# BT840F_Schematic.net
KiCad netlist of a schematic drawn in EAGLE
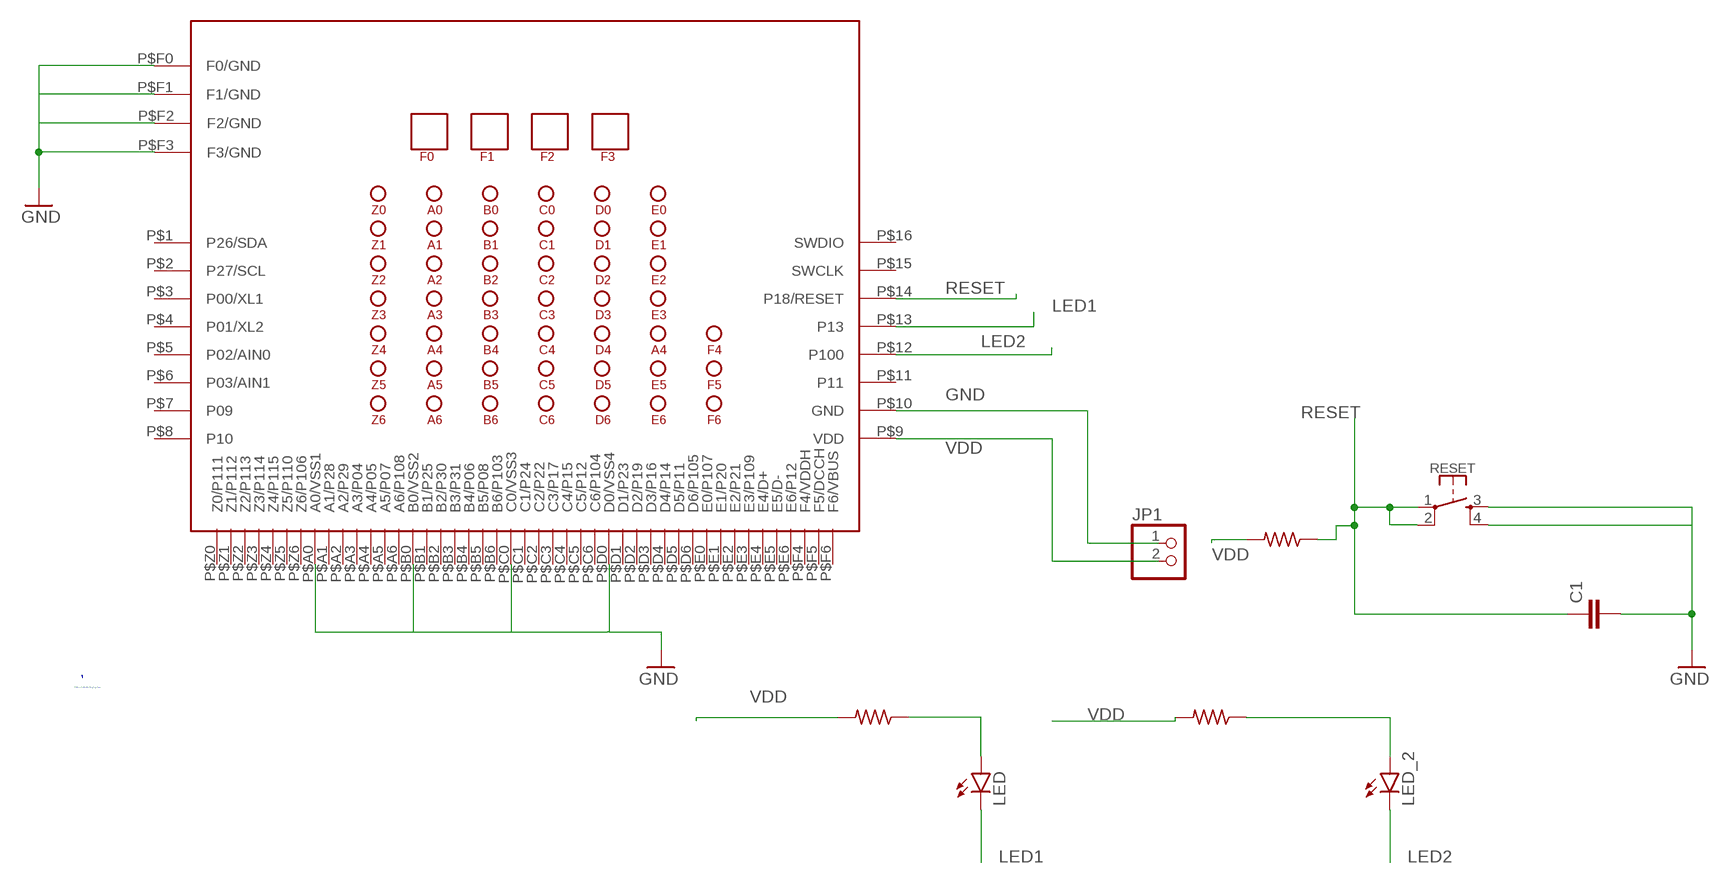
[diagram p0: schematic, sheet 1]

(export (version "E")
  (design (tool "Eeschema 10.0.6"))
  (components
    (comp (ref "C1")
      (value "C-EUC0805")
      (footprint "eagle-import:C0805")
      (libsource (lib "eagle-import") (part "C-EUC0805"))
    )
    (comp (ref "JP1")
      (value "PINHD-1X2")
      (footprint "eagle-import:1X02")
      (libsource (lib "eagle-import") (part "PINHD-1X2"))
    )
    (comp (ref "LED")
      (value "LEDCHIP-LED0805")
      (footprint "eagle-import:CHIP-LED0805")
      (libsource (lib "eagle-import") (part "LEDCHIP-LED0805"))
    )
    (comp (ref "LED_2")
      (value "LEDCHIP-LED0805")
      (footprint "eagle-import:CHIP-LED0805")
      (libsource (lib "eagle-import") (part "LEDCHIP-LED0805"))
    )
    (comp (ref "RESET")
      (value "MOMENTARY-SWITCH-SPST-2-SMD-4.6X2.8MM")
      (footprint "eagle-import:TACTILE_SWITCH_SMD_4.6X2.8MM")
      (libsource (lib "eagle-import") (part "MOMENTARY-SWITCH-SPST-2-SMD-4.6X2.8MM"))
    )
    (comp (ref "R_LED1")
      (value "4.7k")
      (footprint "eagle-import:R0805")
      (libsource (lib "eagle-import") (part "R-US_R0805"))
    )
    (comp (ref "R_LED2")
      (value "4.7k")
      (footprint "eagle-import:R0805")
      (libsource (lib "eagle-import") (part "R-US_R0805"))
    )
    (comp (ref "R_RESET")
      (value "4.7k")
      (footprint "eagle-import:R0805")
      (libsource (lib "eagle-import") (part "R-US_R0805"))
    )
    (comp (ref "U1")
      (value "BT840")
      (footprint "eagle-import:BT840")
      (libsource (lib "eagle-import") (part "BT840"))
    )
  )
  (nets
    (net (code "1") (name "/LED1") (class "Default")
      (node (ref "LED") (pin "C") (pinfunction "C_C") (pintype "passive"))
      (node (ref "U1") (pin "P$13") (pinfunction "P13_P$13") (pintype "bidirectional"))
    )
    (net (code "2") (name "/LED2") (class "Default")
      (node (ref "LED_2") (pin "C") (pinfunction "C_C") (pintype "passive"))
      (node (ref "U1") (pin "P$12") (pinfunction "P100_P$12") (pintype "bidirectional"))
    )
    (net (code "3") (name "/RESET") (class "Default")
      (node (ref "C1") (pin "1") (pinfunction "1_1") (pintype "passive"))
      (node (ref "RESET") (pin "1") (pinfunction "1_1") (pintype "passive"))
      (node (ref "RESET") (pin "2") (pinfunction "2_2") (pintype "passive"))
      (node (ref "R_RESET") (pin "1") (pinfunction "1_1") (pintype "passive"))
      (node (ref "U1") (pin "P$14") (pinfunction "P18/RESET_P$14") (pintype "bidirectional"))
    )
    (net (code "4") (name "/VDD") (class "Default")
      (node (ref "JP1") (pin "2") (pinfunction "2_2") (pintype "passive"))
      (node (ref "R_LED1") (pin "2") (pinfunction "2_2") (pintype "passive"))
      (node (ref "R_LED2") (pin "2") (pinfunction "2_2") (pintype "passive"))
      (node (ref "R_RESET") (pin "2") (pinfunction "2_2") (pintype "passive"))
      (node (ref "U1") (pin "P$9") (pinfunction "VDD_P$9") (pintype "bidirectional"))
    )
    (net (code "5") (name "GND") (class "Default")
      (node (ref "C1") (pin "2") (pinfunction "2_2") (pintype "passive"))
      (node (ref "JP1") (pin "1") (pinfunction "1_1") (pintype "passive"))
      (node (ref "RESET") (pin "3") (pinfunction "3_3") (pintype "passive"))
      (node (ref "RESET") (pin "4") (pinfunction "4_4") (pintype "passive"))
      (node (ref "U1") (pin "P$10") (pinfunction "GND_P$10") (pintype "bidirectional"))
      (node (ref "U1") (pin "P$A0") (pinfunction "A0/VSS1_P$A0") (pintype "bidirectional"))
      (node (ref "U1") (pin "P$B0") (pinfunction "B0/VSS2_P$B0") (pintype "bidirectional"))
      (node (ref "U1") (pin "P$C0") (pinfunction "C0/VSS3_P$C0") (pintype "bidirectional"))
      (node (ref "U1") (pin "P$D0") (pinfunction "D0/VSS4_P$D0") (pintype "bidirectional"))
      (node (ref "U1") (pin "P$F0") (pinfunction "F0/GND_P$F0") (pintype "bidirectional"))
      (node (ref "U1") (pin "P$F1") (pinfunction "F1/GND_P$F1") (pintype "bidirectional"))
      (node (ref "U1") (pin "P$F2") (pinfunction "F2/GND_P$F2") (pintype "bidirectional"))
      (node (ref "U1") (pin "P$F3") (pinfunction "F3/GND_P$F3") (pintype "bidirectional"))
    )
    (net (code "6") (name "Net-(LED-PadA)") (class "Default")
      (node (ref "LED") (pin "A") (pinfunction "A_A") (pintype "passive"))
      (node (ref "R_LED1") (pin "1") (pinfunction "1_1") (pintype "passive"))
    )
    (net (code "7") (name "Net-(LED_2-PadA)") (class "Default")
      (node (ref "LED_2") (pin "A") (pinfunction "A_A") (pintype "passive"))
      (node (ref "R_LED2") (pin "1") (pinfunction "1_1") (pintype "passive"))
    )
    (net (code "8") (name "unconnected-(U1-A1{slash}P28-PadP$A1)") (class "Default")
      (node (ref "U1") (pin "P$A1") (pinfunction "A1/P28_P$A1") (pintype "bidirectional"))
    )
    (net (code "9") (name "unconnected-(U1-A2{slash}P29-PadP$A2)") (class "Default")
      (node (ref "U1") (pin "P$A2") (pinfunction "A2/P29_P$A2") (pintype "bidirectional"))
    )
    (net (code "10") (name "unconnected-(U1-A3{slash}P04-PadP$A3)") (class "Default")
      (node (ref "U1") (pin "P$A3") (pinfunction "A3/P04_P$A3") (pintype "bidirectional"))
    )
    (net (code "11") (name "unconnected-(U1-A4{slash}P05-PadP$A4)") (class "Default")
      (node (ref "U1") (pin "P$A4") (pinfunction "A4/P05_P$A4") (pintype "bidirectional"))
    )
    (net (code "12") (name "unconnected-(U1-A5{slash}P07-PadP$A5)") (class "Default")
      (node (ref "U1") (pin "P$A5") (pinfunction "A5/P07_P$A5") (pintype "bidirectional"))
    )
    (net (code "13") (name "unconnected-(U1-A6{slash}P108-PadP$A6)") (class "Default")
      (node (ref "U1") (pin "P$A6") (pinfunction "A6/P108_P$A6") (pintype "bidirectional"))
    )
    (net (code "14") (name "unconnected-(U1-B1{slash}P25-PadP$B1)") (class "Default")
      (node (ref "U1") (pin "P$B1") (pinfunction "B1/P25_P$B1") (pintype "bidirectional"))
    )
    (net (code "15") (name "unconnected-(U1-B2{slash}P30-PadP$B2)") (class "Default")
      (node (ref "U1") (pin "P$B2") (pinfunction "B2/P30_P$B2") (pintype "bidirectional"))
    )
    (net (code "16") (name "unconnected-(U1-B3{slash}P31-PadP$B3)") (class "Default")
      (node (ref "U1") (pin "P$B3") (pinfunction "B3/P31_P$B3") (pintype "bidirectional"))
    )
    (net (code "17") (name "unconnected-(U1-B4{slash}P06-PadP$B4)") (class "Default")
      (node (ref "U1") (pin "P$B4") (pinfunction "B4/P06_P$B4") (pintype "bidirectional"))
    )
    (net (code "18") (name "unconnected-(U1-B5{slash}P08-PadP$B5)") (class "Default")
      (node (ref "U1") (pin "P$B5") (pinfunction "B5/P08_P$B5") (pintype "bidirectional"))
    )
    (net (code "19") (name "unconnected-(U1-B6{slash}P103-PadP$B6)") (class "Default")
      (node (ref "U1") (pin "P$B6") (pinfunction "B6/P103_P$B6") (pintype "bidirectional"))
    )
    (net (code "20") (name "unconnected-(U1-C1{slash}P24-PadP$C1)") (class "Default")
      (node (ref "U1") (pin "P$C1") (pinfunction "C1/P24_P$C1") (pintype "bidirectional"))
    )
    (net (code "21") (name "unconnected-(U1-C2{slash}P22-PadP$C2)") (class "Default")
      (node (ref "U1") (pin "P$C2") (pinfunction "C2/P22_P$C2") (pintype "bidirectional"))
    )
    (net (code "22") (name "unconnected-(U1-C3{slash}P17-PadP$C3)") (class "Default")
      (node (ref "U1") (pin "P$C3") (pinfunction "C3/P17_P$C3") (pintype "bidirectional"))
    )
    (net (code "23") (name "unconnected-(U1-C4{slash}P15-PadP$C4)") (class "Default")
      (node (ref "U1") (pin "P$C4") (pinfunction "C4/P15_P$C4") (pintype "bidirectional"))
    )
    (net (code "24") (name "unconnected-(U1-C5{slash}P12-PadP$C5)") (class "Default")
      (node (ref "U1") (pin "P$C5") (pinfunction "C5/P12_P$C5") (pintype "bidirectional"))
    )
    (net (code "25") (name "unconnected-(U1-C6{slash}P104-PadP$C6)") (class "Default")
      (node (ref "U1") (pin "P$C6") (pinfunction "C6/P104_P$C6") (pintype "bidirectional"))
    )
    (net (code "26") (name "unconnected-(U1-D1{slash}P23-PadP$D1)") (class "Default")
      (node (ref "U1") (pin "P$D1") (pinfunction "D1/P23_P$D1") (pintype "bidirectional"))
    )
    (net (code "27") (name "unconnected-(U1-D2{slash}P19-PadP$D2)") (class "Default")
      (node (ref "U1") (pin "P$D2") (pinfunction "D2/P19_P$D2") (pintype "bidirectional"))
    )
    (net (code "28") (name "unconnected-(U1-D3{slash}P16-PadP$D3)") (class "Default")
      (node (ref "U1") (pin "P$D3") (pinfunction "D3/P16_P$D3") (pintype "bidirectional"))
    )
    (net (code "29") (name "unconnected-(U1-D4{slash}P14-PadP$D4)") (class "Default")
      (node (ref "U1") (pin "P$D4") (pinfunction "D4/P14_P$D4") (pintype "bidirectional"))
    )
    (net (code "30") (name "unconnected-(U1-D5{slash}P11-PadP$D5)") (class "Default")
      (node (ref "U1") (pin "P$D5") (pinfunction "D5/P11_P$D5") (pintype "bidirectional"))
    )
    (net (code "31") (name "unconnected-(U1-D6{slash}P105-PadP$D6)") (class "Default")
      (node (ref "U1") (pin "P$D6") (pinfunction "D6/P105_P$D6") (pintype "bidirectional"))
    )
    (net (code "32") (name "unconnected-(U1-E0{slash}P107-PadP$E0)") (class "Default")
      (node (ref "U1") (pin "P$E0") (pinfunction "E0/P107_P$E0") (pintype "bidirectional"))
    )
    (net (code "33") (name "unconnected-(U1-E1{slash}P20-PadP$E1)") (class "Default")
      (node (ref "U1") (pin "P$E1") (pinfunction "E1/P20_P$E1") (pintype "bidirectional"))
    )
    (net (code "34") (name "unconnected-(U1-E2{slash}P21-PadP$E2)") (class "Default")
      (node (ref "U1") (pin "P$E2") (pinfunction "E2/P21_P$E2") (pintype "bidirectional"))
    )
    (net (code "35") (name "unconnected-(U1-E3{slash}P109-PadP$E3)") (class "Default")
      (node (ref "U1") (pin "P$E3") (pinfunction "E3/P109_P$E3") (pintype "bidirectional"))
    )
    (net (code "36") (name "unconnected-(U1-E4{slash}D+-PadP$E4)") (class "Default")
      (node (ref "U1") (pin "P$E4") (pinfunction "E4/D+_P$E4") (pintype "bidirectional"))
    )
    (net (code "37") (name "unconnected-(U1-E5{slash}D--PadP$E5)") (class "Default")
      (node (ref "U1") (pin "P$E5") (pinfunction "E5/D-_P$E5") (pintype "bidirectional"))
    )
    (net (code "38") (name "unconnected-(U1-E6{slash}P12-PadP$E6)") (class "Default")
      (node (ref "U1") (pin "P$E6") (pinfunction "E6/P12_P$E6") (pintype "bidirectional"))
    )
    (net (code "39") (name "unconnected-(U1-F4{slash}VDDH-PadP$F4)") (class "Default")
      (node (ref "U1") (pin "P$F4") (pinfunction "F4/VDDH_P$F4") (pintype "bidirectional"))
    )
    (net (code "40") (name "unconnected-(U1-F5{slash}DCCH-PadP$F5)") (class "Default")
      (node (ref "U1") (pin "P$F5") (pinfunction "F5/DCCH_P$F5") (pintype "bidirectional"))
    )
    (net (code "41") (name "unconnected-(U1-F6{slash}VBUS-PadP$F6)") (class "Default")
      (node (ref "U1") (pin "P$F6") (pinfunction "F6/VBUS_P$F6") (pintype "bidirectional"))
    )
    (net (code "42") (name "unconnected-(U1-P00{slash}XL1-PadP$3)") (class "Default")
      (node (ref "U1") (pin "P$3") (pinfunction "P00/XL1_P$3") (pintype "bidirectional"))
    )
    (net (code "43") (name "unconnected-(U1-P01{slash}XL2-PadP$4)") (class "Default")
      (node (ref "U1") (pin "P$4") (pinfunction "P01/XL2_P$4") (pintype "bidirectional"))
    )
    (net (code "44") (name "unconnected-(U1-P02{slash}AIN0-PadP$5)") (class "Default")
      (node (ref "U1") (pin "P$5") (pinfunction "P02/AIN0_P$5") (pintype "bidirectional"))
    )
    (net (code "45") (name "unconnected-(U1-P03{slash}AIN1-PadP$6)") (class "Default")
      (node (ref "U1") (pin "P$6") (pinfunction "P03/AIN1_P$6") (pintype "bidirectional"))
    )
    (net (code "46") (name "unconnected-(U1-P09-PadP$7)") (class "Default")
      (node (ref "U1") (pin "P$7") (pinfunction "P09_P$7") (pintype "bidirectional"))
    )
    (net (code "47") (name "unconnected-(U1-P10-PadP$8)") (class "Default")
      (node (ref "U1") (pin "P$8") (pinfunction "P10_P$8") (pintype "bidirectional"))
    )
    (net (code "48") (name "unconnected-(U1-P11-PadP$11)") (class "Default")
      (node (ref "U1") (pin "P$11") (pinfunction "P11_P$11") (pintype "bidirectional"))
    )
    (net (code "49") (name "unconnected-(U1-P26{slash}SDA-PadP$1)") (class "Default")
      (node (ref "U1") (pin "P$1") (pinfunction "P26/SDA_P$1") (pintype "bidirectional"))
    )
    (net (code "50") (name "unconnected-(U1-P27{slash}SCL-PadP$2)") (class "Default")
      (node (ref "U1") (pin "P$2") (pinfunction "P27/SCL_P$2") (pintype "bidirectional"))
    )
    (net (code "51") (name "unconnected-(U1-SWCLK-PadP$15)") (class "Default")
      (node (ref "U1") (pin "P$15") (pinfunction "SWCLK_P$15") (pintype "bidirectional"))
    )
    (net (code "52") (name "unconnected-(U1-SWDIO-PadP$16)") (class "Default")
      (node (ref "U1") (pin "P$16") (pinfunction "SWDIO_P$16") (pintype "bidirectional"))
    )
    (net (code "53") (name "unconnected-(U1-Z0{slash}P111-PadP$Z0)") (class "Default")
      (node (ref "U1") (pin "P$Z0") (pinfunction "Z0/P111_P$Z0") (pintype "bidirectional"))
    )
    (net (code "54") (name "unconnected-(U1-Z1{slash}P112-PadP$Z1)") (class "Default")
      (node (ref "U1") (pin "P$Z1") (pinfunction "Z1/P112_P$Z1") (pintype "bidirectional"))
    )
    (net (code "55") (name "unconnected-(U1-Z2{slash}P113-PadP$Z2)") (class "Default")
      (node (ref "U1") (pin "P$Z2") (pinfunction "Z2/P113_P$Z2") (pintype "bidirectional"))
    )
    (net (code "56") (name "unconnected-(U1-Z3{slash}P114-PadP$Z3)") (class "Default")
      (node (ref "U1") (pin "P$Z3") (pinfunction "Z3/P114_P$Z3") (pintype "bidirectional"))
    )
    (net (code "57") (name "unconnected-(U1-Z4{slash}P115-PadP$Z4)") (class "Default")
      (node (ref "U1") (pin "P$Z4") (pinfunction "Z4/P115_P$Z4") (pintype "bidirectional"))
    )
    (net (code "58") (name "unconnected-(U1-Z5{slash}P110-PadP$Z5)") (class "Default")
      (node (ref "U1") (pin "P$Z5") (pinfunction "Z5/P110_P$Z5") (pintype "bidirectional"))
    )
    (net (code "59") (name "unconnected-(U1-Z6{slash}P106-PadP$Z6)") (class "Default")
      (node (ref "U1") (pin "P$Z6") (pinfunction "Z6/P106_P$Z6") (pintype "bidirectional"))
    )
  )
)
